# tick-box-1591A-mk-3_1.net
KiCad netlist of a schematic drawn in EAGLE
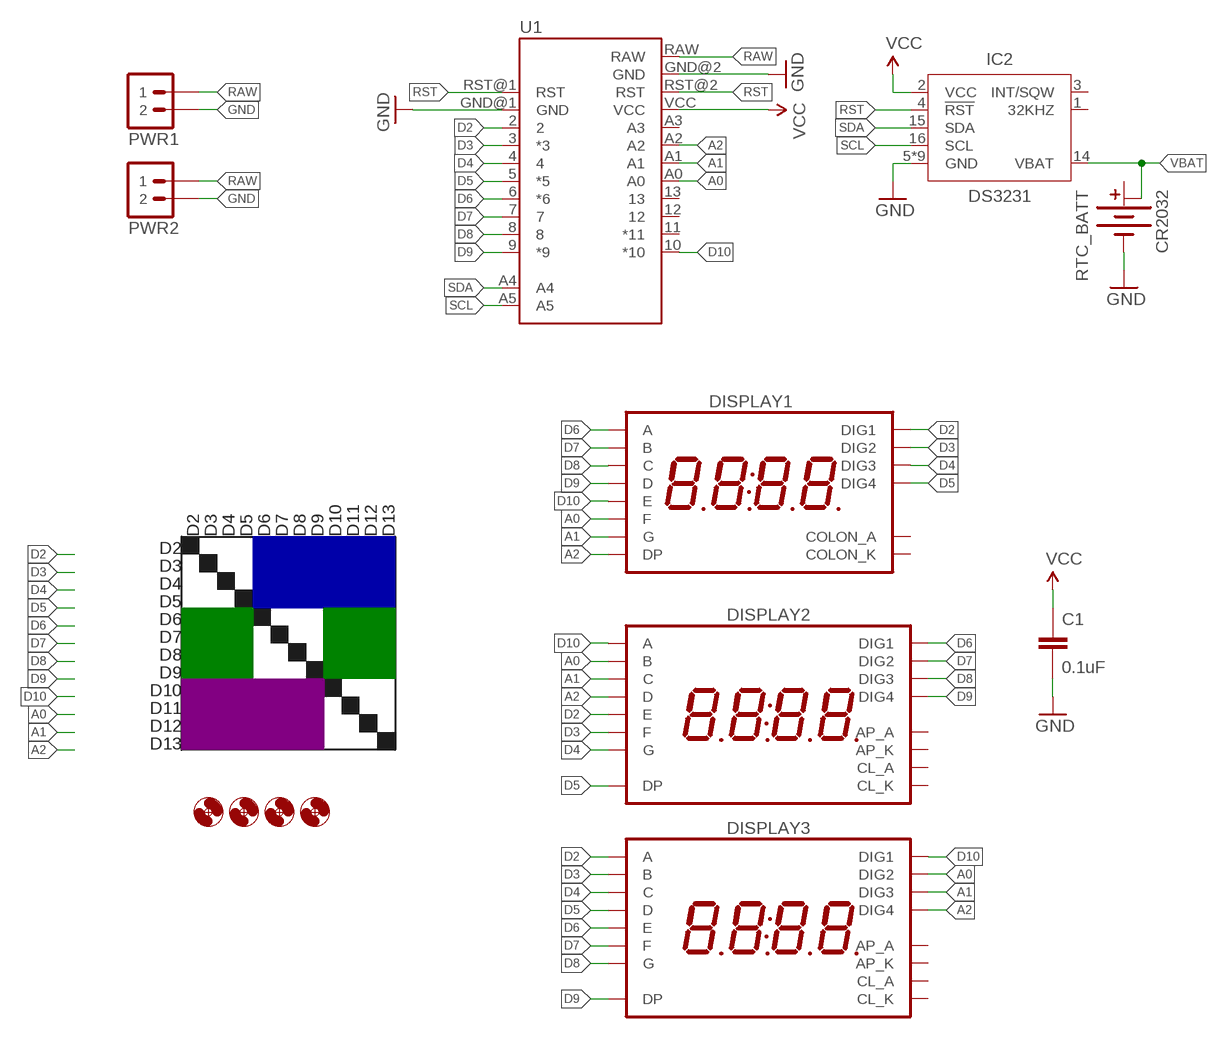
[diagram p0: schematic, sheet 1]

(export (version "E")
  (design (tool "Eeschema 10.0.6"))
  (components
    (comp (ref "C1")
      (value "0.1uF")
      (footprint "eagle-import:C025-024X044")
      (libsource (lib "eagle-import") (part "CAPACITOR-CERAMIC025-024X044"))
    )
    (comp (ref "DISPLAY1")
      (value "7SEG_4DIGIT_COLON14.2MM-CC-NS")
      (footprint "eagle-import:7SEG_4DIG_NS")
      (libsource (lib "eagle-import") (part "7SEG_4DIGIT_COLON14.2MM-CC-NS"))
    )
    (comp (ref "DISPLAY2")
      (value "7SEG_4DIGIT_COLON_APOS")
      (footprint "eagle-import:7SEG_4DIG_10MM")
      (libsource (lib "eagle-import") (part "7SEG_4DIGIT_COLON_APOS"))
    )
    (comp (ref "DISPLAY3")
      (value "7SEG_4DIGIT_COLON_APOS")
      (footprint "eagle-import:7SEG_4DIG_10MM")
      (libsource (lib "eagle-import") (part "7SEG_4DIGIT_COLON_APOS"))
    )
    (comp (ref "H1")
      (value "HOLE#2")
      (footprint "eagle-import:HOLE-#2")
      (libsource (lib "eagle-import") (part "HOLE#2"))
    )
    (comp (ref "H2")
      (value "HOLE#2")
      (footprint "eagle-import:HOLE-#2")
      (libsource (lib "eagle-import") (part "HOLE#2"))
    )
    (comp (ref "H3")
      (value "HOLE#2")
      (footprint "eagle-import:HOLE-#2")
      (libsource (lib "eagle-import") (part "HOLE#2"))
    )
    (comp (ref "H4")
      (value "HOLE#2")
      (footprint "eagle-import:HOLE-#2")
      (libsource (lib "eagle-import") (part "HOLE#2"))
    )
    (comp (ref "IC2")
      (value "DS3231")
      (footprint "eagle-import:SO16W")
      (libsource (lib "eagle-import") (part "DS3231"))
    )
    (comp (ref "PWR1")
      (value "M02PTH-CENTERED")
      (footprint "eagle-import:1X02-CENTER")
      (libsource (lib "eagle-import") (part "M02PTH-CENTERED"))
    )
    (comp (ref "PWR2")
      (value "M02PTH-CENTERED")
      (footprint "eagle-import:1X02-CENTER")
      (libsource (lib "eagle-import") (part "M02PTH-CENTERED"))
    )
    (comp (ref "RTC_BATT")
      (value "CR2032")
      (footprint "eagle-import:BATTCON_20MM_MINE")
      (libsource (lib "eagle-import") (part "BATTERY-COINCR2032_SMD"))
    )
    (comp (ref "U1")
      (value "ARDUINO_PRO_MINI_TICK")
      (footprint "eagle-import:ARDUINO_PRO_MINI_TICK")
      (libsource (lib "eagle-import") (part "ARDUINO_PRO_MINI_TICK"))
    )
  )
  (nets
    (net (code "1") (name "A0") (class "Default")
      (node (ref "DISPLAY1") (pin "P$12") (pinfunction "F_P$12") (pintype "passive"))
      (node (ref "DISPLAY2") (pin "16") (pinfunction "B_16") (pintype "passive"))
      (node (ref "DISPLAY3") (pin "2") (pinfunction "DIG2_2") (pintype "passive"))
      (node (ref "U1") (pin "A0") (pinfunction "A0_A0") (pintype "bidirectional"))
    )
    (net (code "2") (name "A1") (class "Default")
      (node (ref "DISPLAY1") (pin "P$5") (pinfunction "G_P$5") (pintype "passive"))
      (node (ref "DISPLAY2") (pin "13") (pinfunction "C_13") (pintype "passive"))
      (node (ref "DISPLAY3") (pin "6") (pinfunction "DIG3_6") (pintype "passive"))
      (node (ref "U1") (pin "A1") (pinfunction "A1_A1") (pintype "bidirectional"))
    )
    (net (code "3") (name "A2") (class "Default")
      (node (ref "DISPLAY1") (pin "P$3") (pinfunction "DP_P$3") (pintype "passive"))
      (node (ref "DISPLAY2") (pin "3") (pinfunction "D_3") (pintype "passive"))
      (node (ref "DISPLAY3") (pin "8") (pinfunction "DIG4_8") (pintype "passive"))
      (node (ref "U1") (pin "A2") (pinfunction "A2_A2") (pintype "bidirectional"))
    )
    (net (code "4") (name "D2") (class "Default")
      (node (ref "DISPLAY1") (pin "P$14") (pinfunction "DIG1_P$14") (pintype "passive"))
      (node (ref "DISPLAY2") (pin "5") (pinfunction "E_5") (pintype "passive"))
      (node (ref "DISPLAY3") (pin "14") (pinfunction "A_14") (pintype "passive"))
      (node (ref "U1") (pin "2") (pinfunction "2_2") (pintype "bidirectional"))
    )
    (net (code "5") (name "D3") (class "Default")
      (node (ref "DISPLAY1") (pin "P$11") (pinfunction "DIG2_P$11") (pintype "passive"))
      (node (ref "DISPLAY2") (pin "11") (pinfunction "F_11") (pintype "passive"))
      (node (ref "DISPLAY3") (pin "16") (pinfunction "B_16") (pintype "passive"))
      (node (ref "U1") (pin "3") (pinfunction "*3_3") (pintype "bidirectional"))
    )
    (net (code "6") (name "D4") (class "Default")
      (node (ref "DISPLAY1") (pin "P$10") (pinfunction "DIG3_P$10") (pintype "passive"))
      (node (ref "DISPLAY2") (pin "15") (pinfunction "G_15") (pintype "passive"))
      (node (ref "DISPLAY3") (pin "13") (pinfunction "C_13") (pintype "passive"))
      (node (ref "U1") (pin "4") (pinfunction "4_4") (pintype "bidirectional"))
    )
    (net (code "7") (name "D5") (class "Default")
      (node (ref "DISPLAY1") (pin "P$6") (pinfunction "DIG4_P$6") (pintype "passive"))
      (node (ref "DISPLAY2") (pin "7") (pinfunction "DP_7") (pintype "passive"))
      (node (ref "DISPLAY3") (pin "3") (pinfunction "D_3") (pintype "passive"))
      (node (ref "U1") (pin "5") (pinfunction "*5_5") (pintype "bidirectional"))
    )
    (net (code "8") (name "D6") (class "Default")
      (node (ref "DISPLAY1") (pin "P$13") (pinfunction "A_P$13") (pintype "passive"))
      (node (ref "DISPLAY2") (pin "1") (pinfunction "DIG1_1") (pintype "passive"))
      (node (ref "DISPLAY3") (pin "5") (pinfunction "E_5") (pintype "passive"))
      (node (ref "U1") (pin "6") (pinfunction "*6_6") (pintype "bidirectional"))
    )
    (net (code "9") (name "D7") (class "Default")
      (node (ref "DISPLAY1") (pin "P$9") (pinfunction "B_P$9") (pintype "passive"))
      (node (ref "DISPLAY2") (pin "2") (pinfunction "DIG2_2") (pintype "passive"))
      (node (ref "DISPLAY3") (pin "11") (pinfunction "F_11") (pintype "passive"))
      (node (ref "U1") (pin "7") (pinfunction "7_7") (pintype "bidirectional"))
    )
    (net (code "10") (name "D8") (class "Default")
      (node (ref "DISPLAY1") (pin "P$4") (pinfunction "C_P$4") (pintype "passive"))
      (node (ref "DISPLAY2") (pin "6") (pinfunction "DIG3_6") (pintype "passive"))
      (node (ref "DISPLAY3") (pin "15") (pinfunction "G_15") (pintype "passive"))
      (node (ref "U1") (pin "8") (pinfunction "8_8") (pintype "bidirectional"))
    )
    (net (code "11") (name "D9") (class "Default")
      (node (ref "DISPLAY1") (pin "P$2") (pinfunction "D_P$2") (pintype "passive"))
      (node (ref "DISPLAY2") (pin "8") (pinfunction "DIG4_8") (pintype "passive"))
      (node (ref "DISPLAY3") (pin "7") (pinfunction "DP_7") (pintype "passive"))
      (node (ref "U1") (pin "9") (pinfunction "*9_9") (pintype "bidirectional"))
    )
    (net (code "12") (name "D10") (class "Default")
      (node (ref "DISPLAY1") (pin "P$1") (pinfunction "E_P$1") (pintype "passive"))
      (node (ref "DISPLAY2") (pin "14") (pinfunction "A_14") (pintype "passive"))
      (node (ref "DISPLAY3") (pin "1") (pinfunction "DIG1_1") (pintype "passive"))
      (node (ref "U1") (pin "10") (pinfunction "*10_10") (pintype "bidirectional"))
    )
    (net (code "13") (name "GND") (class "Default")
      (node (ref "C1") (pin "2") (pinfunction "2_2") (pintype "passive"))
      (node (ref "IC2") (pin "10") (pinfunction "GND_10") (pintype "bidirectional"))
      (node (ref "IC2") (pin "11") (pinfunction "GND_11") (pintype "bidirectional"))
      (node (ref "IC2") (pin "12") (pinfunction "GND_12") (pintype "bidirectional"))
      (node (ref "IC2") (pin "13") (pinfunction "GND_13") (pintype "bidirectional"))
      (node (ref "IC2") (pin "5") (pinfunction "GND_5") (pintype "bidirectional"))
      (node (ref "IC2") (pin "6") (pinfunction "GND_6") (pintype "bidirectional"))
      (node (ref "IC2") (pin "7") (pinfunction "GND_7") (pintype "bidirectional"))
      (node (ref "IC2") (pin "8") (pinfunction "GND_8") (pintype "bidirectional"))
      (node (ref "IC2") (pin "9") (pinfunction "GND_9") (pintype "bidirectional"))
      (node (ref "PWR1") (pin "2") (pinfunction "2_2") (pintype "passive"))
      (node (ref "PWR2") (pin "2") (pinfunction "2_2") (pintype "passive"))
      (node (ref "RTC_BATT") (pin "BOTTOM") (pinfunction "-_BOTTOM") (pintype "bidirectional"))
      (node (ref "U1") (pin "GND@1") (pinfunction "GND_GND@1") (pintype "bidirectional"))
      (node (ref "U1") (pin "GND@2") (pinfunction "GND_GND@2") (pintype "bidirectional"))
    )
    (net (code "14") (name "RAW") (class "Default")
      (node (ref "PWR1") (pin "1") (pinfunction "1_1") (pintype "passive"))
      (node (ref "PWR2") (pin "1") (pinfunction "1_1") (pintype "passive"))
      (node (ref "U1") (pin "RAW") (pinfunction "RAW_RAW") (pintype "bidirectional"))
    )
    (net (code "15") (name "RST") (class "Default")
      (node (ref "IC2") (pin "4") (pinfunction "~{RST}_4") (pintype "bidirectional"))
      (node (ref "U1") (pin "RST@1") (pinfunction "RST_RST@1") (pintype "bidirectional"))
      (node (ref "U1") (pin "RST@2") (pinfunction "RST_RST@2") (pintype "bidirectional"))
    )
    (net (code "16") (name "SCL") (class "Default")
      (node (ref "IC2") (pin "16") (pinfunction "SCL_16") (pintype "bidirectional"))
      (node (ref "U1") (pin "A5") (pinfunction "A5_A5") (pintype "bidirectional"))
    )
    (net (code "17") (name "SDA") (class "Default")
      (node (ref "IC2") (pin "15") (pinfunction "SDA_15") (pintype "bidirectional"))
      (node (ref "U1") (pin "A4") (pinfunction "A4_A4") (pintype "bidirectional"))
    )
    (net (code "18") (name "VBAT") (class "Default")
      (node (ref "IC2") (pin "14") (pinfunction "VBAT_14") (pintype "bidirectional"))
      (node (ref "RTC_BATT") (pin "TOP@2") (pinfunction "+1_TOP@2") (pintype "bidirectional"))
    )
    (net (code "19") (name "VCC") (class "Default")
      (node (ref "C1") (pin "1") (pinfunction "1_1") (pintype "passive"))
      (node (ref "IC2") (pin "2") (pinfunction "VCC_2") (pintype "bidirectional"))
      (node (ref "U1") (pin "VCC") (pinfunction "VCC_VCC") (pintype "bidirectional"))
    )
    (net (code "20") (name "unconnected-(DISPLAY1-COLON_A-PadP$8)") (class "Default")
      (node (ref "DISPLAY1") (pin "P$8") (pinfunction "COLON_A_P$8") (pintype "passive"))
    )
    (net (code "21") (name "unconnected-(DISPLAY1-COLON_K-PadP$7)") (class "Default")
      (node (ref "DISPLAY1") (pin "P$7") (pinfunction "COLON_K_P$7") (pintype "passive"))
    )
    (net (code "22") (name "unconnected-(DISPLAY2-AP_A-Pad10)") (class "Default")
      (node (ref "DISPLAY2") (pin "10") (pinfunction "AP_A_10") (pintype "bidirectional"))
    )
    (net (code "23") (name "unconnected-(DISPLAY2-AP_K-Pad9)") (class "Default")
      (node (ref "DISPLAY2") (pin "9") (pinfunction "AP_K_9") (pintype "bidirectional"))
    )
    (net (code "24") (name "unconnected-(DISPLAY2-CL_A-Pad4)") (class "Default")
      (node (ref "DISPLAY2") (pin "4") (pinfunction "CL_A_4") (pintype "passive"))
    )
    (net (code "25") (name "unconnected-(DISPLAY2-CL_K-Pad12)") (class "Default")
      (node (ref "DISPLAY2") (pin "12") (pinfunction "CL_K_12") (pintype "passive"))
    )
    (net (code "26") (name "unconnected-(DISPLAY3-AP_A-Pad10)") (class "Default")
      (node (ref "DISPLAY3") (pin "10") (pinfunction "AP_A_10") (pintype "bidirectional"))
    )
    (net (code "27") (name "unconnected-(DISPLAY3-AP_K-Pad9)") (class "Default")
      (node (ref "DISPLAY3") (pin "9") (pinfunction "AP_K_9") (pintype "bidirectional"))
    )
    (net (code "28") (name "unconnected-(DISPLAY3-CL_A-Pad4)") (class "Default")
      (node (ref "DISPLAY3") (pin "4") (pinfunction "CL_A_4") (pintype "passive"))
    )
    (net (code "29") (name "unconnected-(DISPLAY3-CL_K-Pad12)") (class "Default")
      (node (ref "DISPLAY3") (pin "12") (pinfunction "CL_K_12") (pintype "passive"))
    )
    (net (code "30") (name "unconnected-(IC2-32KHZ-Pad1)") (class "Default")
      (node (ref "IC2") (pin "1") (pinfunction "32KHZ_1") (pintype "bidirectional"))
    )
    (net (code "31") (name "unconnected-(IC2-INT{slash}SQW-Pad3)") (class "Default")
      (node (ref "IC2") (pin "3") (pinfunction "INT/SQW_3") (pintype "bidirectional"))
    )
    (net (code "32") (name "unconnected-(RTC_BATT-+-PadTOP@1)") (class "Default")
      (node (ref "RTC_BATT") (pin "TOP@1") (pinfunction "+_TOP@1") (pintype "bidirectional"))
    )
    (net (code "33") (name "unconnected-(U1-*11-Pad11)") (class "Default")
      (node (ref "U1") (pin "11") (pinfunction "*11_11") (pintype "bidirectional"))
    )
    (net (code "34") (name "unconnected-(U1-Pad12)") (class "Default")
      (node (ref "U1") (pin "12") (pinfunction "12_12") (pintype "bidirectional"))
    )
    (net (code "35") (name "unconnected-(U1-Pad13)") (class "Default")
      (node (ref "U1") (pin "13") (pinfunction "13_13") (pintype "bidirectional"))
    )
    (net (code "36") (name "unconnected-(U1-PadA3)") (class "Default")
      (node (ref "U1") (pin "A3") (pinfunction "A3_A3") (pintype "bidirectional"))
    )
  )
)
